# Astable_Sheet.net
KiCad netlist of a schematic drawn in Altium Designer
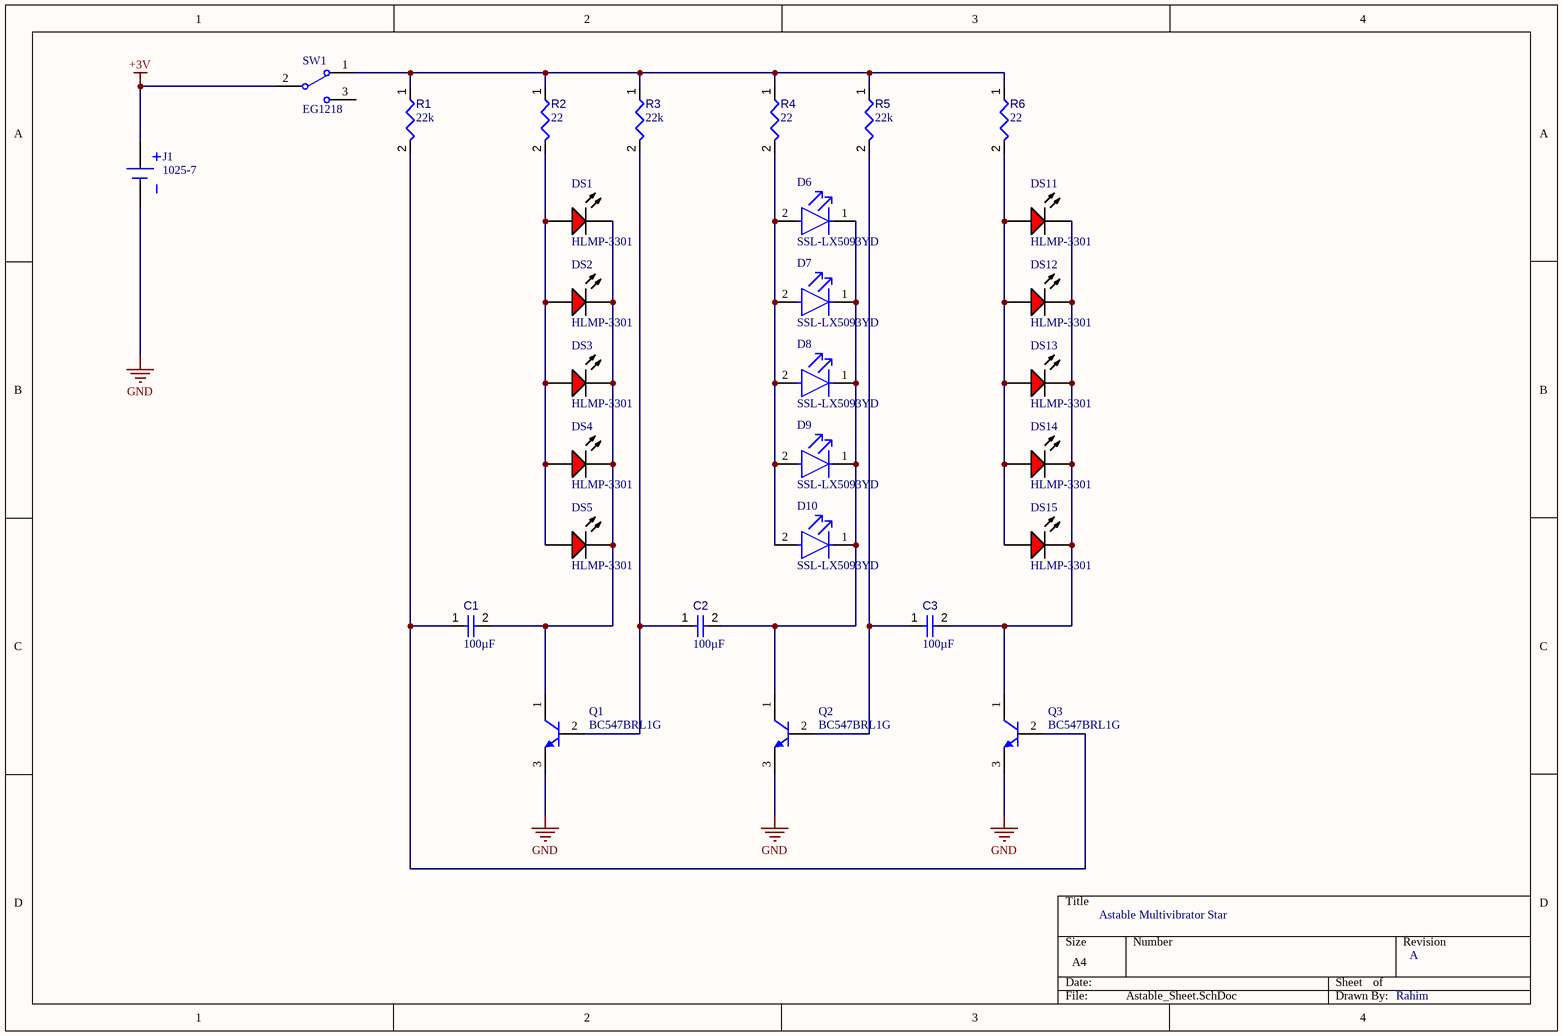
[diagram p0: Astable_Sheet.SchDoc]

(export (version "E")
  (design (tool "Eeschema 10.0.6"))
  (components
    (comp (ref "C1")
      (value "100µF")
      (footprint "CAPC0805(2012)145_L")
      (description "Chip Capacitor, 100µF +/-20%, 6.3V, 0805, Thickness 1.45 mm")
      (fields (field (name "TOLERANCE") "10%") (field (name "Comment") "Capacitor 100µF +/-20% 6.3V 0805"))
      (libsource (lib "McMaster University Workspace") (part "CAP-NP-2"))
    )
    (comp (ref "C2")
      (value "100µF")
      (footprint "CAPC0805(2012)145_L")
      (description "Chip Capacitor, 100µF +/-20%, 6.3V, 0805, Thickness 1.45 mm")
      (fields (field (name "TOLERANCE") "10%") (field (name "Comment") "Capacitor 100µF +/-20% 6.3V 0805"))
      (libsource (lib "McMaster University Workspace") (part "CAP-NP-2"))
    )
    (comp (ref "C3")
      (value "100µF")
      (footprint "CAPC0805(2012)145_L")
      (description "Chip Capacitor, 100µF +/-20%, 6.3V, 0805, Thickness 1.45 mm")
      (fields (field (name "TOLERANCE") "10%") (field (name "Comment") "Capacitor 100µF +/-20% 6.3V 0805"))
      (libsource (lib "McMaster University Workspace") (part "CAP-NP-2"))
    )
    (comp (ref "D6")
      (value "SSL-LX5093YD")
      (footprint "FP-SSL-LX5093YD-MFG")
      (description "LED YELLOW DIFFUSED T-1 3/4 T/H")
      (libsource (lib "Altium Content Vault") (part "8706943c75ba83719d021d2fdc84c58"))
    )
    (comp (ref "D7")
      (value "SSL-LX5093YD")
      (footprint "FP-SSL-LX5093YD-MFG")
      (description "LED YELLOW DIFFUSED T-1 3/4 T/H")
      (libsource (lib "Altium Content Vault") (part "8706943c75ba83719d021d2fdc84c58"))
    )
    (comp (ref "D8")
      (value "SSL-LX5093YD")
      (footprint "FP-SSL-LX5093YD-MFG")
      (description "LED YELLOW DIFFUSED T-1 3/4 T/H")
      (libsource (lib "Altium Content Vault") (part "8706943c75ba83719d021d2fdc84c58"))
    )
    (comp (ref "D9")
      (value "SSL-LX5093YD")
      (footprint "FP-SSL-LX5093YD-MFG")
      (description "LED YELLOW DIFFUSED T-1 3/4 T/H")
      (libsource (lib "Altium Content Vault") (part "8706943c75ba83719d021d2fdc84c58"))
    )
    (comp (ref "D10")
      (value "SSL-LX5093YD")
      (footprint "FP-SSL-LX5093YD-MFG")
      (description "LED YELLOW DIFFUSED T-1 3/4 T/H")
      (libsource (lib "Altium Content Vault") (part "8706943c75ba83719d021d2fdc84c58"))
    )
    (comp (ref "DS1")
      (value "HLMP-3301")
      (footprint "AVAG-HLMP-3301-2")
      (description "T-1 3/4 (5 mm) Diffused LED Lamp, 1.9 V, -40 to 100 degC, 2-Pin THD, RoHS, Bulk")
      (fields (field (name "MANUFACTURER") "Avago"))
      (libsource (lib "Altium Content Vault") (part "LED-RED-K1A2-2"))
    )
    (comp (ref "DS2")
      (value "HLMP-3301")
      (footprint "AVAG-HLMP-3301-2")
      (description "T-1 3/4 (5 mm) Diffused LED Lamp, 1.9 V, -40 to 100 degC, 2-Pin THD, RoHS, Bulk")
      (fields (field (name "MANUFACTURER") "Avago"))
      (libsource (lib "Altium Content Vault") (part "LED-RED-K1A2-2"))
    )
    (comp (ref "DS3")
      (value "HLMP-3301")
      (footprint "AVAG-HLMP-3301-2")
      (description "T-1 3/4 (5 mm) Diffused LED Lamp, 1.9 V, -40 to 100 degC, 2-Pin THD, RoHS, Bulk")
      (fields (field (name "MANUFACTURER") "Avago"))
      (libsource (lib "Altium Content Vault") (part "LED-RED-K1A2-2"))
    )
    (comp (ref "DS4")
      (value "HLMP-3301")
      (footprint "AVAG-HLMP-3301-2")
      (description "T-1 3/4 (5 mm) Diffused LED Lamp, 1.9 V, -40 to 100 degC, 2-Pin THD, RoHS, Bulk")
      (fields (field (name "MANUFACTURER") "Avago"))
      (libsource (lib "Altium Content Vault") (part "LED-RED-K1A2-2"))
    )
    (comp (ref "DS5")
      (value "HLMP-3301")
      (footprint "AVAG-HLMP-3301-2")
      (description "T-1 3/4 (5 mm) Diffused LED Lamp, 1.9 V, -40 to 100 degC, 2-Pin THD, RoHS, Bulk")
      (fields (field (name "MANUFACTURER") "Avago"))
      (libsource (lib "Altium Content Vault") (part "LED-RED-K1A2-2"))
    )
    (comp (ref "DS11")
      (value "HLMP-3301")
      (footprint "AVAG-HLMP-3301-2")
      (description "T-1 3/4 (5 mm) Diffused LED Lamp, 1.9 V, -40 to 100 degC, 2-Pin THD, RoHS, Bulk")
      (fields (field (name "MANUFACTURER") "Avago"))
      (libsource (lib "Altium Content Vault") (part "LED-RED-K1A2-2"))
    )
    (comp (ref "DS12")
      (value "HLMP-3301")
      (footprint "AVAG-HLMP-3301-2")
      (description "T-1 3/4 (5 mm) Diffused LED Lamp, 1.9 V, -40 to 100 degC, 2-Pin THD, RoHS, Bulk")
      (fields (field (name "MANUFACTURER") "Avago"))
      (libsource (lib "Altium Content Vault") (part "LED-RED-K1A2-2"))
    )
    (comp (ref "DS13")
      (value "HLMP-3301")
      (footprint "AVAG-HLMP-3301-2")
      (description "T-1 3/4 (5 mm) Diffused LED Lamp, 1.9 V, -40 to 100 degC, 2-Pin THD, RoHS, Bulk")
      (fields (field (name "MANUFACTURER") "Avago"))
      (libsource (lib "Altium Content Vault") (part "LED-RED-K1A2-2"))
    )
    (comp (ref "DS14")
      (value "HLMP-3301")
      (footprint "AVAG-HLMP-3301-2")
      (description "T-1 3/4 (5 mm) Diffused LED Lamp, 1.9 V, -40 to 100 degC, 2-Pin THD, RoHS, Bulk")
      (fields (field (name "MANUFACTURER") "Avago"))
      (libsource (lib "Altium Content Vault") (part "LED-RED-K1A2-2"))
    )
    (comp (ref "DS15")
      (value "HLMP-3301")
      (footprint "AVAG-HLMP-3301-2")
      (description "T-1 3/4 (5 mm) Diffused LED Lamp, 1.9 V, -40 to 100 degC, 2-Pin THD, RoHS, Bulk")
      (fields (field (name "MANUFACTURER") "Avago"))
      (libsource (lib "Altium Content Vault") (part "LED-RED-K1A2-2"))
    )
    (comp (ref "J1")
      (value "1025-7")
      (footprint "KEYSTONE-1025-7-2_V")
      (description "Holder for 2477 or 2430 Cells P/N 1025-7, Body 27.762 x 30.963 mm, THM")
      (fields (field (name "MANUFACTURER") "Keystone"))
      (libsource (lib "Altium Content Vault") (part "KEYSTONE-1025-7-2"))
    )
    (comp (ref "Q1")
      (value "BC547BRL1G")
      (footprint "ONSC-TO-92-3-29-11_AM_BL")
      (description "Amplifier Transistor, NPN Silicon, 3-Pin TO-92, Pb-Free, Tape and Reel")
      (fields (field (name "MANUFACTURER") "On Semiconductor"))
      (libsource (lib "Altium Content Vault") (part "ONSC-NPN-C1B2E3-3"))
    )
    (comp (ref "Q2")
      (value "BC547BRL1G")
      (footprint "ONSC-TO-92-3-29-11_AM_BL")
      (description "Amplifier Transistor, NPN Silicon, 3-Pin TO-92, Pb-Free, Tape and Reel")
      (fields (field (name "MANUFACTURER") "On Semiconductor"))
      (libsource (lib "Altium Content Vault") (part "ONSC-NPN-C1B2E3-3"))
    )
    (comp (ref "Q3")
      (value "BC547BRL1G")
      (footprint "ONSC-TO-92-3-29-11_AM_BL")
      (description "Amplifier Transistor, NPN Silicon, 3-Pin TO-92, Pb-Free, Tape and Reel")
      (fields (field (name "MANUFACTURER") "On Semiconductor"))
      (libsource (lib "Altium Content Vault") (part "ONSC-NPN-C1B2E3-3"))
    )
    (comp (ref "R1")
      (value "22k")
      (footprint "RESC0402(1005)_L")
      (description "22K 0.063W 1% 0402 (1005 Metric)  SMD")
      (fields (field (name "TOLERANCE") "1%") (field (name "POWER") "63mW"))
      (libsource (lib "McMaster University Workspace") (part "22KR2F"))
    )
    (comp (ref "R2")
      (value "22")
      (footprint "RESC1609X50X30ML08T20")
      (description "Chip Resistor, 22 Ohm, +/- 1%, 100 mW, -55 to 155 degC, 0603 (1608 Metric)")
      (fields (field (name "POWER") "100mW") (field (name "TOLERANCE") "1%"))
      (libsource (lib "McMaster University Workspace") (part "RES-2"))
    )
    (comp (ref "R3")
      (value "22k")
      (footprint "RESC0402(1005)_L")
      (description "22K 0.063W 1% 0402 (1005 Metric)  SMD")
      (fields (field (name "TOLERANCE") "1%") (field (name "POWER") "63mW"))
      (libsource (lib "McMaster University Workspace") (part "22KR2F"))
    )
    (comp (ref "R4")
      (value "22")
      (footprint "RESC1609X50X30ML08T20")
      (description "Chip Resistor, 22 Ohm, +/- 1%, 100 mW, -55 to 155 degC, 0603 (1608 Metric)")
      (fields (field (name "POWER") "100mW") (field (name "TOLERANCE") "1%"))
      (libsource (lib "McMaster University Workspace") (part "RES-2"))
    )
    (comp (ref "R5")
      (value "22k")
      (footprint "RESC0402(1005)_L")
      (description "22K 0.063W 1% 0402 (1005 Metric)  SMD")
      (fields (field (name "TOLERANCE") "1%") (field (name "POWER") "63mW"))
      (libsource (lib "McMaster University Workspace") (part "22KR2F"))
    )
    (comp (ref "R6")
      (value "22")
      (footprint "RESC1609X50X30ML08T20")
      (description "Chip Resistor, 22 Ohm, +/- 1%, 100 mW, -55 to 155 degC, 0603 (1608 Metric)")
      (fields (field (name "POWER") "100mW") (field (name "TOLERANCE") "1%"))
      (libsource (lib "McMaster University Workspace") (part "RES-2"))
    )
    (comp (ref "SW1")
      (value "EG1218")
      (footprint "ESWI-EG1218_V")
      (description "Slide Switch, SPDT, 500 V, -20 to 70 degC, 3-Pin THD, RoHS, Bulk")
      (fields (field (name "MANUFACTURER") "E-Switch"))
      (libsource (lib "McMaster University Workspace") (part "SW-SPDT-3_B"))
    )
  )
  (nets
    (net (code "1") (name "+3V") (class "Default")
      (node (ref "J1") (pin "1") (pinfunction "+_1") (pintype "passive"))
      (node (ref "SW1") (pin "2") (pinfunction "COM_2") (pintype "passive"))
    )
    (net (code "2") (name "GND") (class "Default")
      (node (ref "J1") (pin "2") (pinfunction "-_2") (pintype "passive"))
      (node (ref "Q1") (pin "3") (pinfunction "E_3") (pintype "passive"))
      (node (ref "Q2") (pin "3") (pinfunction "E_3") (pintype "passive"))
      (node (ref "Q3") (pin "3") (pinfunction "E_3") (pintype "passive"))
    )
    (net (code "3") (name "Net-(D10-A)") (class "Default")
      (node (ref "D10") (pin "2") (pinfunction "A_2") (pintype "passive"))
      (node (ref "D6") (pin "2") (pinfunction "A_2") (pintype "passive"))
      (node (ref "D7") (pin "2") (pinfunction "A_2") (pintype "passive"))
      (node (ref "D8") (pin "2") (pinfunction "A_2") (pintype "passive"))
      (node (ref "D9") (pin "2") (pinfunction "A_2") (pintype "passive"))
      (node (ref "R4") (pin "2") (pinfunction "2_2") (pintype "passive"))
    )
    (net (code "4") (name "Net-(D10-C)") (class "Default")
      (node (ref "C2") (pin "2") (pinfunction "2_2") (pintype "passive"))
      (node (ref "D10") (pin "1") (pinfunction "C_1") (pintype "passive"))
      (node (ref "D6") (pin "1") (pinfunction "C_1") (pintype "passive"))
      (node (ref "D7") (pin "1") (pinfunction "C_1") (pintype "passive"))
      (node (ref "D8") (pin "1") (pinfunction "C_1") (pintype "passive"))
      (node (ref "D9") (pin "1") (pinfunction "C_1") (pintype "passive"))
      (node (ref "Q2") (pin "1") (pinfunction "C_1") (pintype "passive"))
    )
    (net (code "5") (name "Net-(DS1-A)") (class "Default")
      (node (ref "DS1") (pin "2") (pinfunction "A_2") (pintype "passive"))
      (node (ref "DS2") (pin "2") (pinfunction "A_2") (pintype "passive"))
      (node (ref "DS3") (pin "2") (pinfunction "A_2") (pintype "passive"))
      (node (ref "DS4") (pin "2") (pinfunction "A_2") (pintype "passive"))
      (node (ref "DS5") (pin "2") (pinfunction "A_2") (pintype "passive"))
      (node (ref "R2") (pin "2") (pinfunction "2_2") (pintype "passive"))
    )
    (net (code "6") (name "Net-(DS1-K)") (class "Default")
      (node (ref "C1") (pin "2") (pinfunction "2_2") (pintype "passive"))
      (node (ref "DS1") (pin "1") (pinfunction "K_1") (pintype "passive"))
      (node (ref "DS2") (pin "1") (pinfunction "K_1") (pintype "passive"))
      (node (ref "DS3") (pin "1") (pinfunction "K_1") (pintype "passive"))
      (node (ref "DS4") (pin "1") (pinfunction "K_1") (pintype "passive"))
      (node (ref "DS5") (pin "1") (pinfunction "K_1") (pintype "passive"))
      (node (ref "Q1") (pin "1") (pinfunction "C_1") (pintype "passive"))
    )
    (net (code "7") (name "Net-(DS11-A)") (class "Default")
      (node (ref "DS11") (pin "2") (pinfunction "A_2") (pintype "passive"))
      (node (ref "DS12") (pin "2") (pinfunction "A_2") (pintype "passive"))
      (node (ref "DS13") (pin "2") (pinfunction "A_2") (pintype "passive"))
      (node (ref "DS14") (pin "2") (pinfunction "A_2") (pintype "passive"))
      (node (ref "DS15") (pin "2") (pinfunction "A_2") (pintype "passive"))
      (node (ref "R6") (pin "2") (pinfunction "2_2") (pintype "passive"))
    )
    (net (code "8") (name "Net-(DS11-K)") (class "Default")
      (node (ref "C3") (pin "2") (pinfunction "2_2") (pintype "passive"))
      (node (ref "DS11") (pin "1") (pinfunction "K_1") (pintype "passive"))
      (node (ref "DS12") (pin "1") (pinfunction "K_1") (pintype "passive"))
      (node (ref "DS13") (pin "1") (pinfunction "K_1") (pintype "passive"))
      (node (ref "DS14") (pin "1") (pinfunction "K_1") (pintype "passive"))
      (node (ref "DS15") (pin "1") (pinfunction "K_1") (pintype "passive"))
      (node (ref "Q3") (pin "1") (pinfunction "C_1") (pintype "passive"))
    )
    (net (code "9") (name "Net-(Q1-B)") (class "Default")
      (node (ref "C2") (pin "1") (pinfunction "1_1") (pintype "passive"))
      (node (ref "Q1") (pin "2") (pinfunction "B_2") (pintype "passive"))
      (node (ref "R3") (pin "2") (pinfunction "2_2") (pintype "passive"))
    )
    (net (code "10") (name "Net-(Q2-B)") (class "Default")
      (node (ref "C3") (pin "1") (pinfunction "1_1") (pintype "passive"))
      (node (ref "Q2") (pin "2") (pinfunction "B_2") (pintype "passive"))
      (node (ref "R5") (pin "2") (pinfunction "2_2") (pintype "passive"))
    )
    (net (code "11") (name "Net-(Q3-B)") (class "Default")
      (node (ref "C1") (pin "1") (pinfunction "1_1") (pintype "passive"))
      (node (ref "Q3") (pin "2") (pinfunction "B_2") (pintype "passive"))
      (node (ref "R1") (pin "2") (pinfunction "2_2") (pintype "passive"))
    )
    (net (code "12") (name "Net-(R1-Pad1)") (class "Default")
      (node (ref "R1") (pin "1") (pinfunction "1_1") (pintype "passive"))
      (node (ref "R2") (pin "1") (pinfunction "1_1") (pintype "passive"))
      (node (ref "R3") (pin "1") (pinfunction "1_1") (pintype "passive"))
      (node (ref "R4") (pin "1") (pinfunction "1_1") (pintype "passive"))
      (node (ref "R5") (pin "1") (pinfunction "1_1") (pintype "passive"))
      (node (ref "R6") (pin "1") (pinfunction "1_1") (pintype "passive"))
      (node (ref "SW1") (pin "1") (pinfunction "1_1") (pintype "passive"))
    )
    (net (code "13") (name "unconnected-(SW1-Pad3)") (class "Default")
      (node (ref "SW1") (pin "3") (pinfunction "3_3") (pintype "passive"))
    )
  )
)
